# Sheet1_-_Copy.net
KiCad netlist of a schematic drawn in Altium Designer
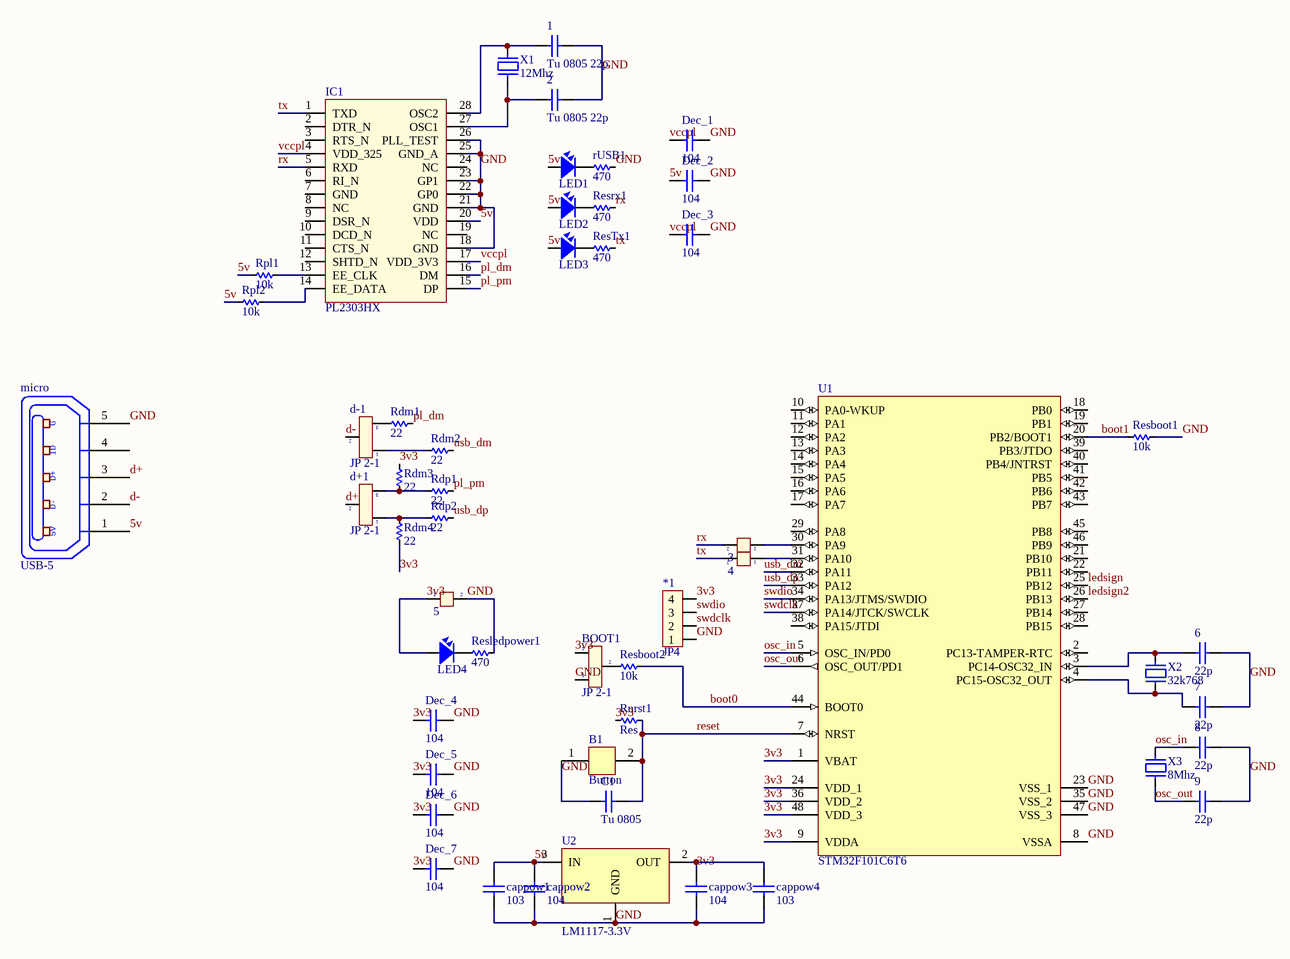
[diagram p0: Sheet1 - Copy.SchDoc]

(export (version "E")
  (design (tool "Eeschema 10.0.6"))
  (components
    (comp (ref "*1")
      (value "JP4")
      (footprint "JP4")
      (libsource (lib "MH_THU VIEN CHUAN 12-03-2015") (part "JP4"))
    )
    (comp (ref "1")
      (value "Tu 0805 22p")
      (footprint "Tu 0805")
      (libsource (lib "MH_THU VIEN CHUAN 12-03-2015") (part "CAP 0805"))
    )
    (comp (ref "2")
      (value "Tu 0805 22p")
      (footprint "Tu 0805")
      (libsource (lib "MH_THU VIEN CHUAN 12-03-2015") (part "CAP 0805"))
    )
    (comp (ref "3")
      (value "Jumper 2")
      (footprint "JP2")
      (libsource (lib "MH_THU VIEN CHUAN 12-03-2015") (part "JP 2"))
    )
    (comp (ref "4")
      (value "Jumper 2")
      (footprint "JP2")
      (libsource (lib "MH_THU VIEN CHUAN 12-03-2015") (part "JP 2"))
    )
    (comp (ref "5") (value "Jumper 2") (footprint "JP2") (libsource (lib "") (part "JP 2_1")))
    (comp (ref "6")
      (value "22p")
      (footprint "Tu 0805")
      (libsource (lib "MH_THU VIEN CHUAN 12-03-2015") (part "CAP 0805"))
    )
    (comp (ref "7")
      (value "22p")
      (footprint "Tu 0805")
      (libsource (lib "MH_THU VIEN CHUAN 12-03-2015") (part "CAP 0805"))
    )
    (comp (ref "8")
      (value "22p")
      (footprint "Tu 0805")
      (libsource (lib "MH_THU VIEN CHUAN 12-03-2015") (part "CAP 0805"))
    )
    (comp (ref "9")
      (value "22p")
      (footprint "Tu 0805")
      (libsource (lib "MH_THU VIEN CHUAN 12-03-2015") (part "CAP 0805"))
    )
    (comp (ref "B1")
      (value "Button")
      (footprint "Button 2 Pin")
      (description "Button 2 pin")
      (libsource (lib "MH_THU VIEN CHUAN 12-03-2015") (part "Button 2 Pin"))
    )
    (comp (ref "BOOT1")
      (value "JP 2-1")
      (footprint "JP3")
      (description "Jumper 2-1")
      (libsource (lib "") (part "JP 2-1_1_1"))
    )
    (comp (ref "C1")
      (value "Tu 0805")
      (footprint "Tu 0805")
      (libsource (lib "MH_THU VIEN CHUAN 12-03-2015") (part "CAP 0805"))
    )
    (comp (ref "cappow1")
      (value "103")
      (footprint "Tu 0805")
      (libsource (lib "MH_THU VIEN CHUAN 12-03-2015") (part "CAP 0805"))
    )
    (comp (ref "cappow2")
      (value "104")
      (footprint "Tu 0805")
      (libsource (lib "MH_THU VIEN CHUAN 12-03-2015") (part "CAP 0805"))
    )
    (comp (ref "cappow3")
      (value "104")
      (footprint "Tu 0805")
      (libsource (lib "MH_THU VIEN CHUAN 12-03-2015") (part "CAP 0805"))
    )
    (comp (ref "cappow4")
      (value "103")
      (footprint "Tu 0805")
      (libsource (lib "MH_THU VIEN CHUAN 12-03-2015") (part "CAP 0805"))
    )
    (comp (ref "d+1")
      (value "JP 2-1")
      (footprint "JP3")
      (description "Jumper 2-1")
      (libsource (lib "MH_THU VIEN CHUAN 12-03-2015") (part "JP 2-1_1"))
    )
    (comp (ref "d-1")
      (value "JP 2-1")
      (footprint "JP3")
      (description "Jumper 2-1")
      (libsource (lib "MH_THU VIEN CHUAN 12-03-2015") (part "JP 2-1_1"))
    )
    (comp (ref "Dec_1")
      (value "104")
      (footprint "Tu 0805")
      (libsource (lib "MH_THU VIEN CHUAN 12-03-2015") (part "CAP 0805"))
    )
    (comp (ref "Dec_2")
      (value "104")
      (footprint "Tu 0805")
      (libsource (lib "MH_THU VIEN CHUAN 12-03-2015") (part "CAP 0805"))
    )
    (comp (ref "Dec_3")
      (value "104")
      (footprint "Tu 0805")
      (libsource (lib "MH_THU VIEN CHUAN 12-03-2015") (part "CAP 0805"))
    )
    (comp (ref "Dec_4")
      (value "104")
      (footprint "Tu 0805")
      (libsource (lib "MH_THU VIEN CHUAN 12-03-2015") (part "CAP 0805"))
    )
    (comp (ref "Dec_5")
      (value "104")
      (footprint "Tu 0805")
      (libsource (lib "MH_THU VIEN CHUAN 12-03-2015") (part "CAP 0805"))
    )
    (comp (ref "Dec_6")
      (value "104")
      (footprint "Tu 0805")
      (libsource (lib "MH_THU VIEN CHUAN 12-03-2015") (part "CAP 0805"))
    )
    (comp (ref "Dec_7")
      (value "104")
      (footprint "Tu 0805")
      (libsource (lib "MH_THU VIEN CHUAN 12-03-2015") (part "CAP 0805"))
    )
    (comp (ref "IC1")
      (value "PL2303HX")
      (footprint "SO-G28/C6.8")
      (description "USB - RS232 Converter")
      (libsource (lib "syhaunguyen") (part "PL2303HX"))
    )
    (comp (ref "LED1")
      (value "LED SMD")
      (footprint "SM-LED-1206-Red")
      (libsource (lib "syhaunguyen") (part "LED-SMD-1206"))
    )
    (comp (ref "LED2")
      (value "LED SMD")
      (footprint "SM-LED-1206-Red")
      (libsource (lib "syhaunguyen") (part "LED-SMD-1206"))
    )
    (comp (ref "LED3")
      (value "LED SMD")
      (footprint "SM-LED-1206-Red")
      (libsource (lib "syhaunguyen") (part "LED-SMD-1206"))
    )
    (comp (ref "LED4")
      (value "LED SMD")
      (footprint "SM-LED-1206-Red")
      (libsource (lib "syhaunguyen") (part "LED-SMD-1206"))
    )
    (comp (ref "micro")
      (value "USB-5")
      (footprint "USB-M1")
      (fields
        (field (name "MANUFACTURER") "FCI")
        (field (name "MANUFACTURER PART NUMBER") "10118193-0001LF")
        (field (name ".CREATOR") "MM")
        (field (name ".CHECKED PCB") "RF")
        (field (name ".CHECKED SCH") "MM")
      )
      (libsource (lib "LIBRARY") (part "USB-5"))
    )
    (comp (ref "Rdm1")
      (value "22")
      (footprint "RES-SMD-0805")
      (description "Resistor")
      (fields
        (field (name "MANUFACTURER") "Generic Components")
        (field (name "PUBLISHER") "Altium Hobart Technology Centre")
      )
      (libsource (lib "LIBRARY") (part "Res-SMD"))
    )
    (comp (ref "Rdm2")
      (value "22")
      (footprint "RES-SMD-0805")
      (description "Resistor")
      (fields
        (field (name "MANUFACTURER") "Generic Components")
        (field (name "PUBLISHER") "Altium Hobart Technology Centre")
      )
      (libsource (lib "LIBRARY") (part "Res-SMD"))
    )
    (comp (ref "Rdm3")
      (value "22")
      (footprint "RES-SMD-0805")
      (description "Resistor")
      (fields
        (field (name "MANUFACTURER") "Generic Components")
        (field (name "PUBLISHER") "Altium Hobart Technology Centre")
      )
      (libsource (lib "LIBRARY") (part "Res-SMD"))
    )
    (comp (ref "Rdm4")
      (value "22")
      (footprint "RES-SMD-0805")
      (description "Resistor")
      (fields
        (field (name "MANUFACTURER") "Generic Components")
        (field (name "PUBLISHER") "Altium Hobart Technology Centre")
      )
      (libsource (lib "LIBRARY") (part "Res-SMD"))
    )
    (comp (ref "Rdp1")
      (value "22")
      (footprint "RES-SMD-0805")
      (description "Resistor")
      (fields
        (field (name "MANUFACTURER") "Generic Components")
        (field (name "PUBLISHER") "Altium Hobart Technology Centre")
      )
      (libsource (lib "LIBRARY") (part "Res-SMD"))
    )
    (comp (ref "Rdp2")
      (value "22")
      (footprint "RES-SMD-0805")
      (description "Resistor")
      (fields
        (field (name "MANUFACTURER") "Generic Components")
        (field (name "PUBLISHER") "Altium Hobart Technology Centre")
      )
      (libsource (lib "LIBRARY") (part "Res-SMD"))
    )
    (comp (ref "Resboot1")
      (value "10k")
      (footprint "RES-SMD-0805")
      (description "Resistor")
      (fields
        (field (name "MANUFACTURER") "Generic Components")
        (field (name "PUBLISHER") "Altium Hobart Technology Centre")
      )
      (libsource (lib "LIBRARY") (part "Res-SMD"))
    )
    (comp (ref "Resboot2")
      (value "10k")
      (footprint "RES-SMD-0805")
      (description "Resistor")
      (fields
        (field (name "MANUFACTURER") "Generic Components")
        (field (name "PUBLISHER") "Altium Hobart Technology Centre")
      )
      (libsource (lib "LIBRARY") (part "Res-SMD"))
    )
    (comp (ref "Resledpower1")
      (value "470")
      (footprint "RES-SMD-0805")
      (description "Resistor")
      (fields
        (field (name "MANUFACTURER") "Generic Components")
        (field (name "PUBLISHER") "Altium Hobart Technology Centre")
      )
      (libsource (lib "LIBRARY") (part "Res-SMD"))
    )
    (comp (ref "Resrx1")
      (value "470")
      (footprint "RES-SMD-0805")
      (description "Resistor")
      (fields
        (field (name "MANUFACTURER") "Generic Components")
        (field (name "PUBLISHER") "Altium Hobart Technology Centre")
      )
      (libsource (lib "LIBRARY") (part "Res-SMD"))
    )
    (comp (ref "ResTx1")
      (value "470")
      (footprint "RES-SMD-0805")
      (description "Resistor")
      (fields
        (field (name "MANUFACTURER") "Generic Components")
        (field (name "PUBLISHER") "Altium Hobart Technology Centre")
      )
      (libsource (lib "LIBRARY") (part "Res-SMD"))
    )
    (comp (ref "Rnrst1")
      (value "Res")
      (footprint "RES-SMD-0805")
      (description "Resistor")
      (fields
        (field (name "MANUFACTURER") "Generic Components")
        (field (name "PUBLISHER") "Altium Hobart Technology Centre")
      )
      (libsource (lib "LIBRARY") (part "Res-SMD"))
    )
    (comp (ref "Rpl1")
      (value "10k")
      (footprint "RES-SMD-0805")
      (description "Resistor")
      (fields
        (field (name "MANUFACTURER") "Generic Components")
        (field (name "PUBLISHER") "Altium Hobart Technology Centre")
      )
      (libsource (lib "LIBRARY") (part "Res-SMD"))
    )
    (comp (ref "Rpl2")
      (value "10k")
      (footprint "RES-SMD-0805")
      (description "Resistor")
      (fields
        (field (name "MANUFACTURER") "Generic Components")
        (field (name "PUBLISHER") "Altium Hobart Technology Centre")
      )
      (libsource (lib "LIBRARY") (part "Res-SMD"))
    )
    (comp (ref "rUSB1")
      (value "470")
      (footprint "RES-SMD-0805")
      (description "Resistor")
      (fields
        (field (name "MANUFACTURER") "Generic Components")
        (field (name "PUBLISHER") "Altium Hobart Technology Centre")
      )
      (libsource (lib "LIBRARY") (part "Res-SMD"))
    )
    (comp (ref "U1")
      (value "STM32F101C6T6")
      (footprint "TQFP48")
      (description "STM32 ARM-based 32-bit MCU with 32 Kbytes Flash, 48-pin LQFP, Industrial Temperature")
      (fields (field (name "PUBLISHER") "Altium Limited"))
      (libsource (lib "LIBRARY") (part "STM32F101C6T6"))
    )
    (comp (ref "U2")
      (value "LM1117-3.3V")
      (footprint "LM1117-SOP")
      (description "800mA Low-Dropout Linear Regulator")
      (fields (field (name "CREATOR") "Nguyen Ba Bien"))
      (libsource (lib "MH_THU VIEN CHUAN 12-03-2015") (part "LM1117"))
    )
    (comp (ref "X1")
      (value "12Mhz")
      (footprint "XT2-SMD")
      (description "Crystal, 32.768 KHz, -40 to 85 degC, 3.2 x 1.5 x 0.9 mm SMD")
      (libsource (lib "LIBRARY") (part "XT2"))
    )
    (comp (ref "X2")
      (value "32k768")
      (footprint "XT32k")
      (description "Crystal, 32.768 KHz, -40 to 85 degC, 3.2 x 1.5 x 0.9 mm SMD")
      (libsource (lib "LIBRARY") (part "XT2"))
    )
    (comp (ref "X3")
      (value "8Mhz")
      (footprint "XT2-SMD")
      (description "Crystal, 32.768 KHz, -40 to 85 degC, 3.2 x 1.5 x 0.9 mm SMD")
      (libsource (lib "LIBRARY") (part "XT2"))
    )
  )
  (nets
    (net (code "1") (name "/3v3") (class "Default")
      (node (ref "*1") (pin "4") (pinfunction "4_4") (pintype "passive"))
      (node (ref "5") (pin "1") (pinfunction "1_1") (pintype "passive"))
      (node (ref "BOOT1") (pin "1") (pinfunction "1_1") (pintype "passive"))
      (node (ref "Dec_4") (pin "1") (pinfunction "1_1") (pintype "passive"))
      (node (ref "Dec_5") (pin "1") (pinfunction "1_1") (pintype "passive"))
      (node (ref "Dec_6") (pin "1") (pinfunction "1_1") (pintype "passive"))
      (node (ref "Dec_7") (pin "1") (pinfunction "1_1") (pintype "passive"))
      (node (ref "LED4") (pin "1") (pinfunction "1_1") (pintype "passive"))
      (node (ref "Rdm3") (pin "1") (pinfunction "1_1") (pintype "passive"))
      (node (ref "Rdm4") (pin "2") (pinfunction "2_2") (pintype "passive"))
      (node (ref "Rnrst1") (pin "2") (pinfunction "2_2") (pintype "passive"))
      (node (ref "U1") (pin "1") (pinfunction "VBAT_1") (pintype "power_in"))
      (node (ref "U1") (pin "24") (pinfunction "VDD_1_24") (pintype "power_in"))
      (node (ref "U1") (pin "36") (pinfunction "VDD_2_36") (pintype "power_in"))
      (node (ref "U1") (pin "48") (pinfunction "VDD_3_48") (pintype "power_in"))
      (node (ref "U1") (pin "9") (pinfunction "VDDA_9") (pintype "power_in"))
      (node (ref "U2") (pin "2") (pinfunction "OUT_2") (pintype "passive"))
      (node (ref "cappow3") (pin "2") (pinfunction "2_2") (pintype "passive"))
      (node (ref "cappow4") (pin "2") (pinfunction "2_2") (pintype "passive"))
    )
    (net (code "2") (name "/5v") (class "Default")
      (node (ref "Dec_2") (pin "1") (pinfunction "1_1") (pintype "passive"))
      (node (ref "IC1") (pin "20") (pinfunction "VDD_20") (pintype "passive"))
      (node (ref "LED1") (pin "1") (pinfunction "1_1") (pintype "passive"))
      (node (ref "LED2") (pin "1") (pinfunction "1_1") (pintype "passive"))
      (node (ref "LED3") (pin "1") (pinfunction "1_1") (pintype "passive"))
      (node (ref "Rpl1") (pin "2") (pinfunction "2_2") (pintype "passive"))
      (node (ref "Rpl2") (pin "2") (pinfunction "2_2") (pintype "passive"))
      (node (ref "U2") (pin "3") (pinfunction "IN_3") (pintype "passive"))
      (node (ref "cappow1") (pin "2") (pinfunction "2_2") (pintype "passive"))
      (node (ref "cappow2") (pin "2") (pinfunction "2_2") (pintype "passive"))
      (node (ref "micro") (pin "1") (pinfunction "P1_1") (pintype "passive"))
    )
    (net (code "3") (name "/GND") (class "Default")
      (node (ref "*1") (pin "1") (pinfunction "1_1") (pintype "passive"))
      (node (ref "1") (pin "2") (pinfunction "2_2") (pintype "passive"))
      (node (ref "2") (pin "2") (pinfunction "2_2") (pintype "passive"))
      (node (ref "5") (pin "2") (pinfunction "2_2") (pintype "passive"))
      (node (ref "6") (pin "2") (pinfunction "2_2") (pintype "passive"))
      (node (ref "7") (pin "2") (pinfunction "2_2") (pintype "passive"))
      (node (ref "8") (pin "2") (pinfunction "2_2") (pintype "passive"))
      (node (ref "9") (pin "2") (pinfunction "2_2") (pintype "passive"))
      (node (ref "B1") (pin "1") (pinfunction "1_1") (pintype "passive"))
      (node (ref "BOOT1") (pin "3") (pinfunction "3_3") (pintype "passive"))
      (node (ref "C1") (pin "2") (pinfunction "2_2") (pintype "passive"))
      (node (ref "Dec_1") (pin "1") (pinfunction "1_1") (pintype "passive"))
      (node (ref "Dec_2") (pin "2") (pinfunction "2_2") (pintype "passive"))
      (node (ref "Dec_3") (pin "2") (pinfunction "2_2") (pintype "passive"))
      (node (ref "Dec_4") (pin "2") (pinfunction "2_2") (pintype "passive"))
      (node (ref "Dec_5") (pin "2") (pinfunction "2_2") (pintype "passive"))
      (node (ref "Dec_6") (pin "2") (pinfunction "2_2") (pintype "passive"))
      (node (ref "Dec_7") (pin "2") (pinfunction "2_2") (pintype "passive"))
      (node (ref "IC1") (pin "18") (pinfunction "GND_18") (pintype "passive"))
      (node (ref "IC1") (pin "21") (pinfunction "GND_21") (pintype "passive"))
      (node (ref "IC1") (pin "22") (pinfunction "GP0_22") (pintype "passive"))
      (node (ref "IC1") (pin "23") (pinfunction "GP1_23") (pintype "passive"))
      (node (ref "IC1") (pin "25") (pinfunction "GND_A_25") (pintype "passive"))
      (node (ref "IC1") (pin "26") (pinfunction "PLL_TEST_26") (pintype "passive"))
      (node (ref "Resboot1") (pin "1") (pinfunction "1_1") (pintype "passive"))
      (node (ref "Resledpower1") (pin "1") (pinfunction "1_1") (pintype "passive"))
      (node (ref "U1") (pin "23") (pinfunction "VSS_1_23") (pintype "power_in"))
      (node (ref "U1") (pin "35") (pinfunction "VSS_2_35") (pintype "power_in"))
      (node (ref "U1") (pin "47") (pinfunction "VSS_3_47") (pintype "power_in"))
      (node (ref "U1") (pin "8") (pinfunction "VSSA_8") (pintype "power_in"))
      (node (ref "U2") (pin "1") (pinfunction "GND_1") (pintype "passive"))
      (node (ref "cappow1") (pin "1") (pinfunction "1_1") (pintype "passive"))
      (node (ref "cappow2") (pin "1") (pinfunction "1_1") (pintype "passive"))
      (node (ref "cappow3") (pin "1") (pinfunction "1_1") (pintype "passive"))
      (node (ref "cappow4") (pin "1") (pinfunction "1_1") (pintype "passive"))
      (node (ref "micro") (pin "5") (pinfunction "P5_5") (pintype "passive"))
      (node (ref "rUSB1") (pin "1") (pinfunction "1_1") (pintype "passive"))
    )
    (net (code "4") (name "/boot0") (class "Default")
      (node (ref "Resboot2") (pin "1") (pinfunction "1_1") (pintype "passive"))
      (node (ref "U1") (pin "44") (pinfunction "BOOT0_44") (pintype "input"))
    )
    (net (code "5") (name "/boot1") (class "Default")
      (node (ref "Resboot1") (pin "2") (pinfunction "2_2") (pintype "passive"))
      (node (ref "U1") (pin "20") (pinfunction "PB2/BOOT1_20") (pintype "bidirectional"))
    )
    (net (code "6") (name "/d+") (class "Default")
      (node (ref "d+1") (pin "2") (pinfunction "2_2") (pintype "passive"))
      (node (ref "micro") (pin "3") (pinfunction "P3_3") (pintype "passive"))
    )
    (net (code "7") (name "/d-") (class "Default")
      (node (ref "d-1") (pin "2") (pinfunction "2_2") (pintype "passive"))
      (node (ref "micro") (pin "2") (pinfunction "P2_2") (pintype "passive"))
    )
    (net (code "8") (name "/ledsign") (class "Default")
      (node (ref "U1") (pin "25") (pinfunction "PB12_25") (pintype "bidirectional"))
    )
    (net (code "9") (name "/ledsign2") (class "Default")
      (node (ref "U1") (pin "26") (pinfunction "PB13_26") (pintype "bidirectional"))
    )
    (net (code "10") (name "/osc_in") (class "Default")
      (node (ref "8") (pin "1") (pinfunction "1_1") (pintype "passive"))
      (node (ref "U1") (pin "5") (pinfunction "OSC_IN/PD0_5") (pintype "input"))
      (node (ref "X3") (pin "2") (pinfunction "2_2") (pintype "passive"))
    )
    (net (code "11") (name "/osc_out") (class "Default")
      (node (ref "9") (pin "1") (pinfunction "1_1") (pintype "passive"))
      (node (ref "U1") (pin "6") (pinfunction "OSC_OUT/PD1_6") (pintype "output"))
      (node (ref "X3") (pin "1") (pinfunction "1_1") (pintype "passive"))
    )
    (net (code "12") (name "/pl_dm") (class "Default")
      (node (ref "IC1") (pin "16") (pinfunction "DM_16") (pintype "passive"))
      (node (ref "Rdm1") (pin "1") (pinfunction "1_1") (pintype "passive"))
    )
    (net (code "13") (name "/pl_pm") (class "Default")
      (node (ref "IC1") (pin "15") (pinfunction "DP_15") (pintype "passive"))
      (node (ref "Rdp1") (pin "1") (pinfunction "1_1") (pintype "passive"))
    )
    (net (code "14") (name "/reset") (class "Default")
      (node (ref "B1") (pin "2") (pinfunction "2_2") (pintype "passive"))
      (node (ref "C1") (pin "1") (pinfunction "1_1") (pintype "passive"))
      (node (ref "Rnrst1") (pin "1") (pinfunction "1_1") (pintype "passive"))
      (node (ref "U1") (pin "7") (pinfunction "NRST_7") (pintype "bidirectional"))
    )
    (net (code "15") (name "/rx") (class "Default")
      (node (ref "3") (pin "2") (pinfunction "2_2") (pintype "passive"))
      (node (ref "IC1") (pin "5") (pinfunction "RXD_5") (pintype "passive"))
      (node (ref "Resrx1") (pin "1") (pinfunction "1_1") (pintype "passive"))
    )
    (net (code "16") (name "/swdclk") (class "Default")
      (node (ref "*1") (pin "2") (pinfunction "2_2") (pintype "passive"))
      (node (ref "U1") (pin "37") (pinfunction "PA14/JTCK/SWCLK_37") (pintype "bidirectional"))
    )
    (net (code "17") (name "/swdio") (class "Default")
      (node (ref "*1") (pin "3") (pinfunction "3_3") (pintype "passive"))
      (node (ref "U1") (pin "34") (pinfunction "PA13/JTMS/SWDIO_34") (pintype "bidirectional"))
    )
    (net (code "18") (name "/tx") (class "Default")
      (node (ref "4") (pin "2") (pinfunction "2_2") (pintype "passive"))
      (node (ref "IC1") (pin "1") (pinfunction "TXD_1") (pintype "passive"))
      (node (ref "ResTx1") (pin "1") (pinfunction "1_1") (pintype "passive"))
    )
    (net (code "19") (name "/usb_dm") (class "Default")
      (node (ref "Rdm2") (pin "1") (pinfunction "1_1") (pintype "passive"))
      (node (ref "U1") (pin "32") (pinfunction "PA11_32") (pintype "bidirectional"))
    )
    (net (code "20") (name "/usb_dp") (class "Default")
      (node (ref "Rdp2") (pin "1") (pinfunction "1_1") (pintype "passive"))
      (node (ref "U1") (pin "33") (pinfunction "PA12_33") (pintype "bidirectional"))
    )
    (net (code "21") (name "/vccpl") (class "Default")
      (node (ref "Dec_1") (pin "2") (pinfunction "2_2") (pintype "passive"))
      (node (ref "Dec_3") (pin "1") (pinfunction "1_1") (pintype "passive"))
      (node (ref "IC1") (pin "17") (pinfunction "VDD_3V3_17") (pintype "passive"))
      (node (ref "IC1") (pin "4") (pinfunction "VDD_325_4") (pintype "passive"))
    )
    (net (code "22") (name "Net-(BOOT1-Pad2)") (class "Default")
      (node (ref "BOOT1") (pin "2") (pinfunction "2_2") (pintype "passive"))
      (node (ref "Resboot2") (pin "2") (pinfunction "2_2") (pintype "passive"))
    )
    (net (code "23") (name "Net-(IC1-EE_CLK)") (class "Default")
      (node (ref "IC1") (pin "13") (pinfunction "EE_CLK_13") (pintype "passive"))
      (node (ref "Rpl1") (pin "1") (pinfunction "1_1") (pintype "passive"))
    )
    (net (code "24") (name "Net-(IC1-EE_DATA)") (class "Default")
      (node (ref "IC1") (pin "14") (pinfunction "EE_DATA_14") (pintype "passive"))
      (node (ref "Rpl2") (pin "1") (pinfunction "1_1") (pintype "passive"))
    )
    (net (code "25") (name "Net-(IC1-OSC1)") (class "Default")
      (node (ref "2") (pin "1") (pinfunction "1_1") (pintype "passive"))
      (node (ref "IC1") (pin "27") (pinfunction "OSC1_27") (pintype "passive"))
      (node (ref "X1") (pin "1") (pinfunction "1_1") (pintype "passive"))
    )
    (net (code "26") (name "Net-(IC1-OSC2)") (class "Default")
      (node (ref "1") (pin "1") (pinfunction "1_1") (pintype "passive"))
      (node (ref "IC1") (pin "28") (pinfunction "OSC2_28") (pintype "passive"))
      (node (ref "X1") (pin "2") (pinfunction "2_2") (pintype "passive"))
    )
    (net (code "27") (name "Net-(LED1-Pad2)") (class "Default")
      (node (ref "LED1") (pin "2") (pinfunction "2_2") (pintype "passive"))
      (node (ref "rUSB1") (pin "2") (pinfunction "2_2") (pintype "passive"))
    )
    (net (code "28") (name "Net-(LED2-Pad2)") (class "Default")
      (node (ref "LED2") (pin "2") (pinfunction "2_2") (pintype "passive"))
      (node (ref "Resrx1") (pin "2") (pinfunction "2_2") (pintype "passive"))
    )
    (net (code "29") (name "Net-(LED3-Pad2)") (class "Default")
      (node (ref "LED3") (pin "2") (pinfunction "2_2") (pintype "passive"))
      (node (ref "ResTx1") (pin "2") (pinfunction "2_2") (pintype "passive"))
    )
    (net (code "30") (name "Net-(LED4-Pad2)") (class "Default")
      (node (ref "LED4") (pin "2") (pinfunction "2_2") (pintype "passive"))
      (node (ref "Resledpower1") (pin "2") (pinfunction "2_2") (pintype "passive"))
    )
    (net (code "31") (name "Net-(Rdm1-Pad2)") (class "Default")
      (node (ref "Rdm1") (pin "2") (pinfunction "2_2") (pintype "passive"))
      (node (ref "d-1") (pin "3") (pinfunction "3_3") (pintype "passive"))
    )
    (net (code "32") (name "Net-(Rdm2-Pad2)") (class "Default")
      (node (ref "Rdm2") (pin "2") (pinfunction "2_2") (pintype "passive"))
      (node (ref "d-1") (pin "1") (pinfunction "1_1") (pintype "passive"))
    )
    (net (code "33") (name "Net-(Rdm3-Pad2)") (class "Default")
      (node (ref "Rdm3") (pin "2") (pinfunction "2_2") (pintype "passive"))
      (node (ref "Rdp1") (pin "2") (pinfunction "2_2") (pintype "passive"))
      (node (ref "d+1") (pin "3") (pinfunction "3_3") (pintype "passive"))
    )
    (net (code "34") (name "Net-(Rdm4-Pad1)") (class "Default")
      (node (ref "Rdm4") (pin "1") (pinfunction "1_1") (pintype "passive"))
      (node (ref "Rdp2") (pin "2") (pinfunction "2_2") (pintype "passive"))
      (node (ref "d+1") (pin "1") (pinfunction "1_1") (pintype "passive"))
    )
    (net (code "35") (name "Net-(U1-PA9)") (class "Default")
      (node (ref "3") (pin "1") (pinfunction "1_1") (pintype "passive"))
      (node (ref "U1") (pin "30") (pinfunction "PA9_30") (pintype "bidirectional"))
    )
    (net (code "36") (name "Net-(U1-PA10)") (class "Default")
      (node (ref "4") (pin "1") (pinfunction "1_1") (pintype "passive"))
      (node (ref "U1") (pin "31") (pinfunction "PA10_31") (pintype "bidirectional"))
    )
    (net (code "37") (name "Net-(U1-PC14-OSC32_IN)") (class "Default")
      (node (ref "6") (pin "1") (pinfunction "1_1") (pintype "passive"))
      (node (ref "U1") (pin "3") (pinfunction "PC14-OSC32_IN_3") (pintype "bidirectional"))
      (node (ref "X2") (pin "2") (pinfunction "2_2") (pintype "passive"))
    )
    (net (code "38") (name "Net-(U1-PC15-OSC32_OUT)") (class "Default")
      (node (ref "7") (pin "1") (pinfunction "1_1") (pintype "passive"))
      (node (ref "U1") (pin "4") (pinfunction "PC15-OSC32_OUT_4") (pintype "bidirectional"))
      (node (ref "X2") (pin "1") (pinfunction "1_1") (pintype "passive"))
    )
    (net (code "39") (name "unconnected-(IC1-CTS_N-Pad11)") (class "Default")
      (node (ref "IC1") (pin "11") (pinfunction "CTS_N_11") (pintype "passive"))
    )
    (net (code "40") (name "unconnected-(IC1-DCD_N-Pad10)") (class "Default")
      (node (ref "IC1") (pin "10") (pinfunction "DCD_N_10") (pintype "passive"))
    )
    (net (code "41") (name "unconnected-(IC1-DSR_N-Pad9)") (class "Default")
      (node (ref "IC1") (pin "9") (pinfunction "DSR_N_9") (pintype "passive"))
    )
    (net (code "42") (name "unconnected-(IC1-DTR_N-Pad2)") (class "Default")
      (node (ref "IC1") (pin "2") (pinfunction "DTR_N_2") (pintype "passive"))
    )
    (net (code "43") (name "unconnected-(IC1-GND-Pad7)") (class "Default")
      (node (ref "IC1") (pin "7") (pinfunction "GND_7") (pintype "passive"))
    )
    (net (code "44") (name "unconnected-(IC1-NC-Pad8)") (class "Default")
      (node (ref "IC1") (pin "8") (pinfunction "NC_8") (pintype "passive"))
    )
    (net (code "45") (name "unconnected-(IC1-NC-Pad19)") (class "Default")
      (node (ref "IC1") (pin "19") (pinfunction "NC_19") (pintype "passive"))
    )
    (net (code "46") (name "unconnected-(IC1-NC-Pad24)") (class "Default")
      (node (ref "IC1") (pin "24") (pinfunction "NC_24") (pintype "passive"))
    )
    (net (code "47") (name "unconnected-(IC1-RI_N-Pad6)") (class "Default")
      (node (ref "IC1") (pin "6") (pinfunction "RI_N_6") (pintype "passive"))
    )
    (net (code "48") (name "unconnected-(IC1-RTS_N-Pad3)") (class "Default")
      (node (ref "IC1") (pin "3") (pinfunction "RTS_N_3") (pintype "passive"))
    )
    (net (code "49") (name "unconnected-(IC1-SHTD_N-Pad12)") (class "Default")
      (node (ref "IC1") (pin "12") (pinfunction "SHTD_N_12") (pintype "passive"))
    )
    (net (code "50") (name "unconnected-(U1-PA0-WKUP-Pad10)") (class "Default")
      (node (ref "U1") (pin "10") (pinfunction "PA0-WKUP_10") (pintype "bidirectional"))
    )
    (net (code "51") (name "unconnected-(U1-PA1-Pad11)") (class "Default")
      (node (ref "U1") (pin "11") (pinfunction "PA1_11") (pintype "bidirectional"))
    )
    (net (code "52") (name "unconnected-(U1-PA2-Pad12)") (class "Default")
      (node (ref "U1") (pin "12") (pinfunction "PA2_12") (pintype "bidirectional"))
    )
    (net (code "53") (name "unconnected-(U1-PA3-Pad13)") (class "Default")
      (node (ref "U1") (pin "13") (pinfunction "PA3_13") (pintype "bidirectional"))
    )
    (net (code "54") (name "unconnected-(U1-PA4-Pad14)") (class "Default")
      (node (ref "U1") (pin "14") (pinfunction "PA4_14") (pintype "bidirectional"))
    )
    (net (code "55") (name "unconnected-(U1-PA5-Pad15)") (class "Default")
      (node (ref "U1") (pin "15") (pinfunction "PA5_15") (pintype "bidirectional"))
    )
    (net (code "56") (name "unconnected-(U1-PA6-Pad16)") (class "Default")
      (node (ref "U1") (pin "16") (pinfunction "PA6_16") (pintype "bidirectional"))
    )
    (net (code "57") (name "unconnected-(U1-PA7-Pad17)") (class "Default")
      (node (ref "U1") (pin "17") (pinfunction "PA7_17") (pintype "bidirectional"))
    )
    (net (code "58") (name "unconnected-(U1-PA8-Pad29)") (class "Default")
      (node (ref "U1") (pin "29") (pinfunction "PA8_29") (pintype "bidirectional"))
    )
    (net (code "59") (name "unconnected-(U1-PA15{slash}JTDI-Pad38)") (class "Default")
      (node (ref "U1") (pin "38") (pinfunction "PA15/JTDI_38") (pintype "bidirectional"))
    )
    (net (code "60") (name "unconnected-(U1-PB0-Pad18)") (class "Default")
      (node (ref "U1") (pin "18") (pinfunction "PB0_18") (pintype "bidirectional"))
    )
    (net (code "61") (name "unconnected-(U1-PB1-Pad19)") (class "Default")
      (node (ref "U1") (pin "19") (pinfunction "PB1_19") (pintype "bidirectional"))
    )
    (net (code "62") (name "unconnected-(U1-PB3{slash}JTDO-Pad39)") (class "Default")
      (node (ref "U1") (pin "39") (pinfunction "PB3/JTDO_39") (pintype "bidirectional"))
    )
    (net (code "63") (name "unconnected-(U1-PB4{slash}JNTRST-Pad40)") (class "Default")
      (node (ref "U1") (pin "40") (pinfunction "PB4/JNTRST_40") (pintype "bidirectional"))
    )
    (net (code "64") (name "unconnected-(U1-PB5-Pad41)") (class "Default")
      (node (ref "U1") (pin "41") (pinfunction "PB5_41") (pintype "bidirectional"))
    )
    (net (code "65") (name "unconnected-(U1-PB6-Pad42)") (class "Default")
      (node (ref "U1") (pin "42") (pinfunction "PB6_42") (pintype "bidirectional"))
    )
    (net (code "66") (name "unconnected-(U1-PB7-Pad43)") (class "Default")
      (node (ref "U1") (pin "43") (pinfunction "PB7_43") (pintype "bidirectional"))
    )
    (net (code "67") (name "unconnected-(U1-PB8-Pad45)") (class "Default")
      (node (ref "U1") (pin "45") (pinfunction "PB8_45") (pintype "bidirectional"))
    )
    (net (code "68") (name "unconnected-(U1-PB9-Pad46)") (class "Default")
      (node (ref "U1") (pin "46") (pinfunction "PB9_46") (pintype "bidirectional"))
    )
    (net (code "69") (name "unconnected-(U1-PB10-Pad21)") (class "Default")
      (node (ref "U1") (pin "21") (pinfunction "PB10_21") (pintype "bidirectional"))
    )
    (net (code "70") (name "unconnected-(U1-PB11-Pad22)") (class "Default")
      (node (ref "U1") (pin "22") (pinfunction "PB11_22") (pintype "bidirectional"))
    )
    (net (code "71") (name "unconnected-(U1-PB14-Pad27)") (class "Default")
      (node (ref "U1") (pin "27") (pinfunction "PB14_27") (pintype "bidirectional"))
    )
    (net (code "72") (name "unconnected-(U1-PB15-Pad28)") (class "Default")
      (node (ref "U1") (pin "28") (pinfunction "PB15_28") (pintype "bidirectional"))
    )
    (net (code "73") (name "unconnected-(U1-PC13-TAMPER-RTC-Pad2)") (class "Default")
      (node (ref "U1") (pin "2") (pinfunction "PC13-TAMPER-RTC_2") (pintype "bidirectional"))
    )
    (net (code "74") (name "unconnected-(micro-P4-Pad4)") (class "Default")
      (node (ref "micro") (pin "4") (pinfunction "P4_4") (pintype "passive"))
    )
  )
)
